# BaseBoard.net
KiCad netlist of a schematic drawn in EAGLE
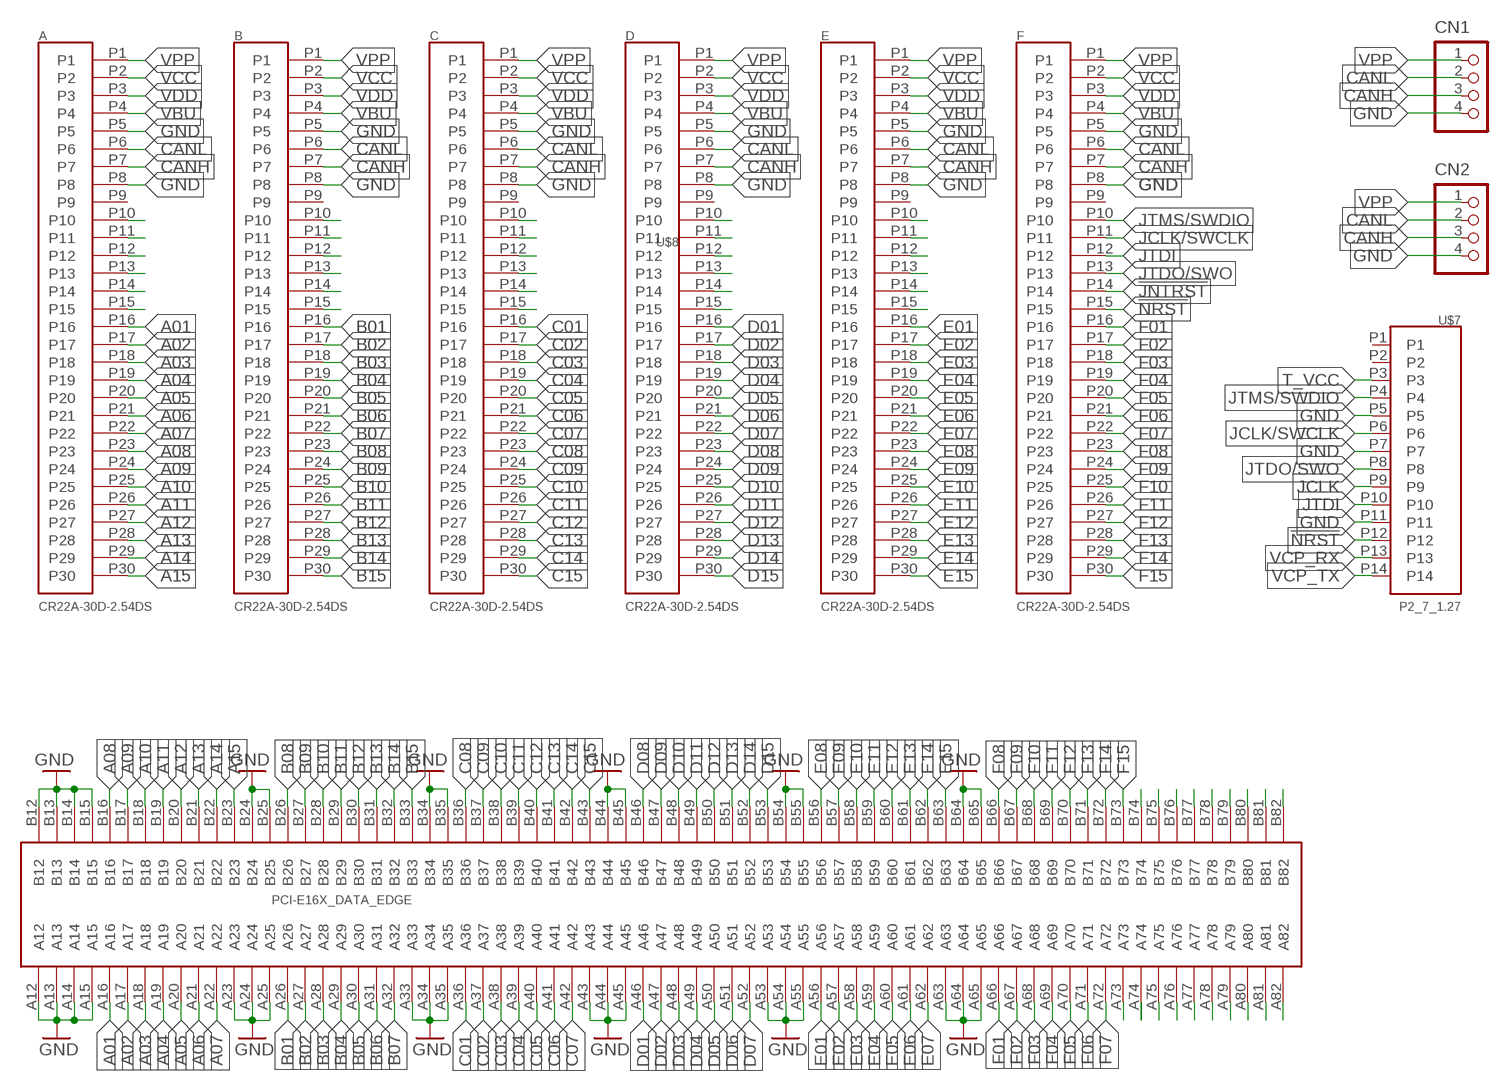
[diagram p0: schematic, sheet 1]

(export (version "E")
  (design (tool "Eeschema 10.0.6"))
  (components
    (comp (ref "A")
      (value "CR22A-30D-2.54DS")
      (footprint "eagle-import:CR22A-30D-2.54DS")
      (libsource (lib "eagle-import") (part "CR22A-30D-2.54DS"))
    )
    (comp (ref "B")
      (value "CR22A-30D-2.54DS")
      (footprint "eagle-import:CR22A-30D-2.54DS")
      (libsource (lib "eagle-import") (part "CR22A-30D-2.54DS"))
    )
    (comp (ref "C")
      (value "CR22A-30D-2.54DS")
      (footprint "eagle-import:CR22A-30D-2.54DS")
      (libsource (lib "eagle-import") (part "CR22A-30D-2.54DS"))
    )
    (comp (ref "CN1")
      (value "B4B-PH-K-S")
      (footprint "eagle-import:B4B-PH-K-S")
      (libsource (lib "eagle-import") (part "B4B-PH-K-S"))
    )
    (comp (ref "CN2")
      (value "B4B-PH-K-S")
      (footprint "eagle-import:B4B-PH-K-S")
      (libsource (lib "eagle-import") (part "B4B-PH-K-S"))
    )
    (comp (ref "D")
      (value "CR22A-30D-2.54DS")
      (footprint "eagle-import:CR22A-30D-2.54DS")
      (libsource (lib "eagle-import") (part "CR22A-30D-2.54DS"))
    )
    (comp (ref "E")
      (value "CR22A-30D-2.54DS")
      (footprint "eagle-import:CR22A-30D-2.54DS")
      (libsource (lib "eagle-import") (part "CR22A-30D-2.54DS"))
    )
    (comp (ref "F")
      (value "CR22A-30D-2.54DS")
      (footprint "eagle-import:CR22A-30D-2.54DS")
      (libsource (lib "eagle-import") (part "CR22A-30D-2.54DS"))
    )
    (comp (ref "U$7")
      (value "P2_7_1.27")
      (footprint "eagle-import:P2_7_1.27")
      (libsource (lib "eagle-import") (part "P2_7_1.27"))
    )
    (comp (ref "U$8")
      (value "PCI-E16X_DATA_EDGE")
      (footprint "eagle-import:PCI-E_164_DATA_EDGE")
      (libsource (lib "eagle-import") (part "PCI-E16X_DATA_EDGE"))
    )
  )
  (nets
    (net (code "1") (name "/~{JNTRST}") (class "Default")
      (node (ref "F") (pin "P14") (pinfunction "P14_P14") (pintype "bidirectional"))
    )
    (net (code "2") (name "/~{NRST}") (class "Default")
      (node (ref "F") (pin "P15") (pinfunction "P15_P15") (pintype "bidirectional"))
      (node (ref "U$7") (pin "P12") (pinfunction "P12_P12") (pintype "bidirectional"))
    )
    (net (code "3") (name "A01") (class "Default")
      (node (ref "A") (pin "P16") (pinfunction "P16_P16") (pintype "bidirectional"))
      (node (ref "U$8") (pin "A16") (pinfunction "A16_A16") (pintype "bidirectional"))
    )
    (net (code "4") (name "A02") (class "Default")
      (node (ref "A") (pin "P17") (pinfunction "P17_P17") (pintype "bidirectional"))
      (node (ref "U$8") (pin "A17") (pinfunction "A17_A17") (pintype "bidirectional"))
    )
    (net (code "5") (name "A03") (class "Default")
      (node (ref "A") (pin "P18") (pinfunction "P18_P18") (pintype "bidirectional"))
      (node (ref "U$8") (pin "A18") (pinfunction "A18_A18") (pintype "bidirectional"))
    )
    (net (code "6") (name "A04") (class "Default")
      (node (ref "A") (pin "P19") (pinfunction "P19_P19") (pintype "bidirectional"))
      (node (ref "U$8") (pin "A19") (pinfunction "A19_A19") (pintype "bidirectional"))
    )
    (net (code "7") (name "A05") (class "Default")
      (node (ref "A") (pin "P20") (pinfunction "P20_P20") (pintype "bidirectional"))
      (node (ref "U$8") (pin "A20") (pinfunction "A20_A20") (pintype "bidirectional"))
    )
    (net (code "8") (name "A06") (class "Default")
      (node (ref "A") (pin "P21") (pinfunction "P21_P21") (pintype "bidirectional"))
      (node (ref "U$8") (pin "A21") (pinfunction "A21_A21") (pintype "bidirectional"))
    )
    (net (code "9") (name "A07") (class "Default")
      (node (ref "A") (pin "P22") (pinfunction "P22_P22") (pintype "bidirectional"))
      (node (ref "U$8") (pin "A22") (pinfunction "A22_A22") (pintype "bidirectional"))
    )
    (net (code "10") (name "A08") (class "Default")
      (node (ref "A") (pin "P23") (pinfunction "P23_P23") (pintype "bidirectional"))
      (node (ref "U$8") (pin "B16") (pinfunction "B16_B16") (pintype "bidirectional"))
    )
    (net (code "11") (name "A09") (class "Default")
      (node (ref "A") (pin "P24") (pinfunction "P24_P24") (pintype "bidirectional"))
      (node (ref "U$8") (pin "B17") (pinfunction "B17_B17") (pintype "bidirectional"))
    )
    (net (code "12") (name "A10") (class "Default")
      (node (ref "A") (pin "P25") (pinfunction "P25_P25") (pintype "bidirectional"))
      (node (ref "U$8") (pin "B18") (pinfunction "B18_B18") (pintype "bidirectional"))
    )
    (net (code "13") (name "A11") (class "Default")
      (node (ref "A") (pin "P26") (pinfunction "P26_P26") (pintype "bidirectional"))
      (node (ref "U$8") (pin "B19") (pinfunction "B19_B19") (pintype "bidirectional"))
    )
    (net (code "14") (name "A12") (class "Default")
      (node (ref "A") (pin "P27") (pinfunction "P27_P27") (pintype "bidirectional"))
      (node (ref "U$8") (pin "B20") (pinfunction "B20_B20") (pintype "bidirectional"))
    )
    (net (code "15") (name "A13") (class "Default")
      (node (ref "A") (pin "P28") (pinfunction "P28_P28") (pintype "bidirectional"))
      (node (ref "U$8") (pin "B21") (pinfunction "B21_B21") (pintype "bidirectional"))
    )
    (net (code "16") (name "A14") (class "Default")
      (node (ref "A") (pin "P29") (pinfunction "P29_P29") (pintype "bidirectional"))
      (node (ref "U$8") (pin "B22") (pinfunction "B22_B22") (pintype "bidirectional"))
    )
    (net (code "17") (name "A15") (class "Default")
      (node (ref "A") (pin "P30") (pinfunction "P30_P30") (pintype "bidirectional"))
      (node (ref "U$8") (pin "B23") (pinfunction "B23_B23") (pintype "bidirectional"))
    )
    (net (code "18") (name "B01") (class "Default")
      (node (ref "B") (pin "P16") (pinfunction "P16_P16") (pintype "bidirectional"))
      (node (ref "U$8") (pin "A26") (pinfunction "A26_A26") (pintype "bidirectional"))
    )
    (net (code "19") (name "B02") (class "Default")
      (node (ref "B") (pin "P17") (pinfunction "P17_P17") (pintype "bidirectional"))
      (node (ref "U$8") (pin "A27") (pinfunction "A27_A27") (pintype "bidirectional"))
    )
    (net (code "20") (name "B03") (class "Default")
      (node (ref "B") (pin "P18") (pinfunction "P18_P18") (pintype "bidirectional"))
      (node (ref "U$8") (pin "A28") (pinfunction "A28_A28") (pintype "bidirectional"))
    )
    (net (code "21") (name "B04") (class "Default")
      (node (ref "B") (pin "P19") (pinfunction "P19_P19") (pintype "bidirectional"))
      (node (ref "U$8") (pin "A29") (pinfunction "A29_A29") (pintype "bidirectional"))
    )
    (net (code "22") (name "B05") (class "Default")
      (node (ref "B") (pin "P20") (pinfunction "P20_P20") (pintype "bidirectional"))
      (node (ref "U$8") (pin "A30") (pinfunction "A30_A30") (pintype "bidirectional"))
    )
    (net (code "23") (name "B06") (class "Default")
      (node (ref "B") (pin "P21") (pinfunction "P21_P21") (pintype "bidirectional"))
      (node (ref "U$8") (pin "A31") (pinfunction "A31_A31") (pintype "bidirectional"))
    )
    (net (code "24") (name "B07") (class "Default")
      (node (ref "B") (pin "P22") (pinfunction "P22_P22") (pintype "bidirectional"))
      (node (ref "U$8") (pin "A32") (pinfunction "A32_A32") (pintype "bidirectional"))
    )
    (net (code "25") (name "B08") (class "Default")
      (node (ref "B") (pin "P23") (pinfunction "P23_P23") (pintype "bidirectional"))
      (node (ref "U$8") (pin "B26") (pinfunction "B26_B26") (pintype "bidirectional"))
    )
    (net (code "26") (name "B09") (class "Default")
      (node (ref "B") (pin "P24") (pinfunction "P24_P24") (pintype "bidirectional"))
      (node (ref "U$8") (pin "B27") (pinfunction "B27_B27") (pintype "bidirectional"))
    )
    (net (code "27") (name "B10") (class "Default")
      (node (ref "B") (pin "P25") (pinfunction "P25_P25") (pintype "bidirectional"))
      (node (ref "U$8") (pin "B28") (pinfunction "B28_B28") (pintype "bidirectional"))
    )
    (net (code "28") (name "B11") (class "Default")
      (node (ref "B") (pin "P26") (pinfunction "P26_P26") (pintype "bidirectional"))
      (node (ref "U$8") (pin "B29") (pinfunction "B29_B29") (pintype "bidirectional"))
    )
    (net (code "29") (name "B12") (class "Default")
      (node (ref "B") (pin "P27") (pinfunction "P27_P27") (pintype "bidirectional"))
      (node (ref "U$8") (pin "B30") (pinfunction "B30_B30") (pintype "bidirectional"))
    )
    (net (code "30") (name "B13") (class "Default")
      (node (ref "B") (pin "P28") (pinfunction "P28_P28") (pintype "bidirectional"))
      (node (ref "U$8") (pin "B31") (pinfunction "B31_B31") (pintype "bidirectional"))
    )
    (net (code "31") (name "B14") (class "Default")
      (node (ref "B") (pin "P29") (pinfunction "P29_P29") (pintype "bidirectional"))
      (node (ref "U$8") (pin "B32") (pinfunction "B32_B32") (pintype "bidirectional"))
    )
    (net (code "32") (name "B15") (class "Default")
      (node (ref "B") (pin "P30") (pinfunction "P30_P30") (pintype "bidirectional"))
      (node (ref "U$8") (pin "B33") (pinfunction "B33_B33") (pintype "bidirectional"))
    )
    (net (code "33") (name "C01") (class "Default")
      (node (ref "C") (pin "P16") (pinfunction "P16_P16") (pintype "bidirectional"))
      (node (ref "U$8") (pin "A36") (pinfunction "A36_A36") (pintype "bidirectional"))
    )
    (net (code "34") (name "C02") (class "Default")
      (node (ref "C") (pin "P17") (pinfunction "P17_P17") (pintype "bidirectional"))
      (node (ref "U$8") (pin "A37") (pinfunction "A37_A37") (pintype "bidirectional"))
    )
    (net (code "35") (name "C03") (class "Default")
      (node (ref "C") (pin "P18") (pinfunction "P18_P18") (pintype "bidirectional"))
      (node (ref "U$8") (pin "A38") (pinfunction "A38_A38") (pintype "bidirectional"))
    )
    (net (code "36") (name "C04") (class "Default")
      (node (ref "C") (pin "P19") (pinfunction "P19_P19") (pintype "bidirectional"))
      (node (ref "U$8") (pin "A39") (pinfunction "A39_A39") (pintype "bidirectional"))
    )
    (net (code "37") (name "C05") (class "Default")
      (node (ref "C") (pin "P20") (pinfunction "P20_P20") (pintype "bidirectional"))
      (node (ref "U$8") (pin "A40") (pinfunction "A40_A40") (pintype "bidirectional"))
    )
    (net (code "38") (name "C06") (class "Default")
      (node (ref "C") (pin "P21") (pinfunction "P21_P21") (pintype "bidirectional"))
      (node (ref "U$8") (pin "A41") (pinfunction "A41_A41") (pintype "bidirectional"))
    )
    (net (code "39") (name "C07") (class "Default")
      (node (ref "C") (pin "P22") (pinfunction "P22_P22") (pintype "bidirectional"))
      (node (ref "U$8") (pin "A42") (pinfunction "A42_A42") (pintype "bidirectional"))
    )
    (net (code "40") (name "C08") (class "Default")
      (node (ref "C") (pin "P23") (pinfunction "P23_P23") (pintype "bidirectional"))
      (node (ref "U$8") (pin "B36") (pinfunction "B36_B36") (pintype "bidirectional"))
    )
    (net (code "41") (name "C09") (class "Default")
      (node (ref "C") (pin "P24") (pinfunction "P24_P24") (pintype "bidirectional"))
      (node (ref "U$8") (pin "B37") (pinfunction "B37_B37") (pintype "bidirectional"))
    )
    (net (code "42") (name "C10") (class "Default")
      (node (ref "C") (pin "P25") (pinfunction "P25_P25") (pintype "bidirectional"))
      (node (ref "U$8") (pin "B38") (pinfunction "B38_B38") (pintype "bidirectional"))
    )
    (net (code "43") (name "C11") (class "Default")
      (node (ref "C") (pin "P26") (pinfunction "P26_P26") (pintype "bidirectional"))
      (node (ref "U$8") (pin "B39") (pinfunction "B39_B39") (pintype "bidirectional"))
    )
    (net (code "44") (name "C12") (class "Default")
      (node (ref "C") (pin "P27") (pinfunction "P27_P27") (pintype "bidirectional"))
      (node (ref "U$8") (pin "B40") (pinfunction "B40_B40") (pintype "bidirectional"))
    )
    (net (code "45") (name "C13") (class "Default")
      (node (ref "C") (pin "P28") (pinfunction "P28_P28") (pintype "bidirectional"))
      (node (ref "U$8") (pin "B41") (pinfunction "B41_B41") (pintype "bidirectional"))
    )
    (net (code "46") (name "C14") (class "Default")
      (node (ref "C") (pin "P29") (pinfunction "P29_P29") (pintype "bidirectional"))
      (node (ref "U$8") (pin "B42") (pinfunction "B42_B42") (pintype "bidirectional"))
    )
    (net (code "47") (name "C15") (class "Default")
      (node (ref "C") (pin "P30") (pinfunction "P30_P30") (pintype "bidirectional"))
      (node (ref "U$8") (pin "B43") (pinfunction "B43_B43") (pintype "bidirectional"))
    )
    (net (code "48") (name "CANH") (class "Default")
      (node (ref "A") (pin "P7") (pinfunction "P7_P7") (pintype "bidirectional"))
      (node (ref "B") (pin "P7") (pinfunction "P7_P7") (pintype "bidirectional"))
      (node (ref "C") (pin "P7") (pinfunction "P7_P7") (pintype "bidirectional"))
      (node (ref "CN1") (pin "3") (pinfunction "3_3") (pintype "passive"))
      (node (ref "CN2") (pin "3") (pinfunction "3_3") (pintype "passive"))
      (node (ref "D") (pin "P7") (pinfunction "P7_P7") (pintype "bidirectional"))
      (node (ref "E") (pin "P7") (pinfunction "P7_P7") (pintype "bidirectional"))
      (node (ref "F") (pin "P7") (pinfunction "P7_P7") (pintype "bidirectional"))
    )
    (net (code "49") (name "CANL") (class "Default")
      (node (ref "A") (pin "P6") (pinfunction "P6_P6") (pintype "bidirectional"))
      (node (ref "B") (pin "P6") (pinfunction "P6_P6") (pintype "bidirectional"))
      (node (ref "C") (pin "P6") (pinfunction "P6_P6") (pintype "bidirectional"))
      (node (ref "CN1") (pin "2") (pinfunction "2_2") (pintype "passive"))
      (node (ref "CN2") (pin "2") (pinfunction "2_2") (pintype "passive"))
      (node (ref "D") (pin "P6") (pinfunction "P6_P6") (pintype "bidirectional"))
      (node (ref "E") (pin "P6") (pinfunction "P6_P6") (pintype "bidirectional"))
      (node (ref "F") (pin "P6") (pinfunction "P6_P6") (pintype "bidirectional"))
    )
    (net (code "50") (name "D01") (class "Default")
      (node (ref "D") (pin "P16") (pinfunction "P16_P16") (pintype "bidirectional"))
      (node (ref "U$8") (pin "A46") (pinfunction "A46_A46") (pintype "bidirectional"))
    )
    (net (code "51") (name "D02") (class "Default")
      (node (ref "D") (pin "P17") (pinfunction "P17_P17") (pintype "bidirectional"))
      (node (ref "U$8") (pin "A47") (pinfunction "A47_A47") (pintype "bidirectional"))
    )
    (net (code "52") (name "D03") (class "Default")
      (node (ref "D") (pin "P18") (pinfunction "P18_P18") (pintype "bidirectional"))
      (node (ref "U$8") (pin "A48") (pinfunction "A48_A48") (pintype "bidirectional"))
    )
    (net (code "53") (name "D04") (class "Default")
      (node (ref "D") (pin "P19") (pinfunction "P19_P19") (pintype "bidirectional"))
      (node (ref "U$8") (pin "A49") (pinfunction "A49_A49") (pintype "bidirectional"))
    )
    (net (code "54") (name "D05") (class "Default")
      (node (ref "D") (pin "P20") (pinfunction "P20_P20") (pintype "bidirectional"))
      (node (ref "U$8") (pin "A50") (pinfunction "A50_A50") (pintype "bidirectional"))
    )
    (net (code "55") (name "D06") (class "Default")
      (node (ref "D") (pin "P21") (pinfunction "P21_P21") (pintype "bidirectional"))
      (node (ref "U$8") (pin "A51") (pinfunction "A51_A51") (pintype "bidirectional"))
    )
    (net (code "56") (name "D07") (class "Default")
      (node (ref "D") (pin "P22") (pinfunction "P22_P22") (pintype "bidirectional"))
      (node (ref "U$8") (pin "A52") (pinfunction "A52_A52") (pintype "bidirectional"))
    )
    (net (code "57") (name "D08") (class "Default")
      (node (ref "D") (pin "P23") (pinfunction "P23_P23") (pintype "bidirectional"))
      (node (ref "U$8") (pin "B46") (pinfunction "B46_B46") (pintype "bidirectional"))
    )
    (net (code "58") (name "D09") (class "Default")
      (node (ref "D") (pin "P24") (pinfunction "P24_P24") (pintype "bidirectional"))
      (node (ref "U$8") (pin "B47") (pinfunction "B47_B47") (pintype "bidirectional"))
    )
    (net (code "59") (name "D10") (class "Default")
      (node (ref "D") (pin "P25") (pinfunction "P25_P25") (pintype "bidirectional"))
      (node (ref "U$8") (pin "B48") (pinfunction "B48_B48") (pintype "bidirectional"))
    )
    (net (code "60") (name "D11") (class "Default")
      (node (ref "D") (pin "P26") (pinfunction "P26_P26") (pintype "bidirectional"))
      (node (ref "U$8") (pin "B49") (pinfunction "B49_B49") (pintype "bidirectional"))
    )
    (net (code "61") (name "D12") (class "Default")
      (node (ref "D") (pin "P27") (pinfunction "P27_P27") (pintype "bidirectional"))
      (node (ref "U$8") (pin "B50") (pinfunction "B50_B50") (pintype "bidirectional"))
    )
    (net (code "62") (name "D13") (class "Default")
      (node (ref "D") (pin "P28") (pinfunction "P28_P28") (pintype "bidirectional"))
      (node (ref "U$8") (pin "B51") (pinfunction "B51_B51") (pintype "bidirectional"))
    )
    (net (code "63") (name "D14") (class "Default")
      (node (ref "D") (pin "P29") (pinfunction "P29_P29") (pintype "bidirectional"))
      (node (ref "U$8") (pin "B52") (pinfunction "B52_B52") (pintype "bidirectional"))
    )
    (net (code "64") (name "D15") (class "Default")
      (node (ref "D") (pin "P30") (pinfunction "P30_P30") (pintype "bidirectional"))
      (node (ref "U$8") (pin "B53") (pinfunction "B53_B53") (pintype "bidirectional"))
    )
    (net (code "65") (name "E01") (class "Default")
      (node (ref "E") (pin "P16") (pinfunction "P16_P16") (pintype "bidirectional"))
      (node (ref "U$8") (pin "A56") (pinfunction "A56_A56") (pintype "bidirectional"))
    )
    (net (code "66") (name "E02") (class "Default")
      (node (ref "E") (pin "P17") (pinfunction "P17_P17") (pintype "bidirectional"))
      (node (ref "U$8") (pin "A57") (pinfunction "A57_A57") (pintype "bidirectional"))
    )
    (net (code "67") (name "E03") (class "Default")
      (node (ref "E") (pin "P18") (pinfunction "P18_P18") (pintype "bidirectional"))
      (node (ref "U$8") (pin "A58") (pinfunction "A58_A58") (pintype "bidirectional"))
    )
    (net (code "68") (name "E04") (class "Default")
      (node (ref "E") (pin "P19") (pinfunction "P19_P19") (pintype "bidirectional"))
      (node (ref "U$8") (pin "A59") (pinfunction "A59_A59") (pintype "bidirectional"))
    )
    (net (code "69") (name "E05") (class "Default")
      (node (ref "E") (pin "P20") (pinfunction "P20_P20") (pintype "bidirectional"))
      (node (ref "U$8") (pin "A60") (pinfunction "A60_A60") (pintype "bidirectional"))
    )
    (net (code "70") (name "E06") (class "Default")
      (node (ref "E") (pin "P21") (pinfunction "P21_P21") (pintype "bidirectional"))
      (node (ref "U$8") (pin "A61") (pinfunction "A61_A61") (pintype "bidirectional"))
    )
    (net (code "71") (name "E07") (class "Default")
      (node (ref "E") (pin "P22") (pinfunction "P22_P22") (pintype "bidirectional"))
      (node (ref "U$8") (pin "A62") (pinfunction "A62_A62") (pintype "bidirectional"))
    )
    (net (code "72") (name "E08") (class "Default")
      (node (ref "E") (pin "P23") (pinfunction "P23_P23") (pintype "bidirectional"))
      (node (ref "U$8") (pin "B56") (pinfunction "B56_B56") (pintype "bidirectional"))
    )
    (net (code "73") (name "E09") (class "Default")
      (node (ref "E") (pin "P24") (pinfunction "P24_P24") (pintype "bidirectional"))
      (node (ref "U$8") (pin "B57") (pinfunction "B57_B57") (pintype "bidirectional"))
    )
    (net (code "74") (name "E10") (class "Default")
      (node (ref "E") (pin "P25") (pinfunction "P25_P25") (pintype "bidirectional"))
      (node (ref "U$8") (pin "B58") (pinfunction "B58_B58") (pintype "bidirectional"))
    )
    (net (code "75") (name "E11") (class "Default")
      (node (ref "E") (pin "P26") (pinfunction "P26_P26") (pintype "bidirectional"))
      (node (ref "U$8") (pin "B59") (pinfunction "B59_B59") (pintype "bidirectional"))
    )
    (net (code "76") (name "E12") (class "Default")
      (node (ref "E") (pin "P27") (pinfunction "P27_P27") (pintype "bidirectional"))
      (node (ref "U$8") (pin "B60") (pinfunction "B60_B60") (pintype "bidirectional"))
    )
    (net (code "77") (name "E13") (class "Default")
      (node (ref "E") (pin "P28") (pinfunction "P28_P28") (pintype "bidirectional"))
      (node (ref "U$8") (pin "B61") (pinfunction "B61_B61") (pintype "bidirectional"))
    )
    (net (code "78") (name "E14") (class "Default")
      (node (ref "E") (pin "P29") (pinfunction "P29_P29") (pintype "bidirectional"))
      (node (ref "U$8") (pin "B62") (pinfunction "B62_B62") (pintype "bidirectional"))
    )
    (net (code "79") (name "E15") (class "Default")
      (node (ref "E") (pin "P30") (pinfunction "P30_P30") (pintype "bidirectional"))
      (node (ref "U$8") (pin "B63") (pinfunction "B63_B63") (pintype "bidirectional"))
    )
    (net (code "80") (name "F01") (class "Default")
      (node (ref "F") (pin "P16") (pinfunction "P16_P16") (pintype "bidirectional"))
      (node (ref "U$8") (pin "A66") (pinfunction "A66_A66") (pintype "bidirectional"))
    )
    (net (code "81") (name "F02") (class "Default")
      (node (ref "F") (pin "P17") (pinfunction "P17_P17") (pintype "bidirectional"))
      (node (ref "U$8") (pin "A67") (pinfunction "A67_A67") (pintype "bidirectional"))
    )
    (net (code "82") (name "F03") (class "Default")
      (node (ref "F") (pin "P18") (pinfunction "P18_P18") (pintype "bidirectional"))
      (node (ref "U$8") (pin "A68") (pinfunction "A68_A68") (pintype "bidirectional"))
    )
    (net (code "83") (name "F04") (class "Default")
      (node (ref "F") (pin "P19") (pinfunction "P19_P19") (pintype "bidirectional"))
      (node (ref "U$8") (pin "A69") (pinfunction "A69_A69") (pintype "bidirectional"))
    )
    (net (code "84") (name "F05") (class "Default")
      (node (ref "F") (pin "P20") (pinfunction "P20_P20") (pintype "bidirectional"))
      (node (ref "U$8") (pin "A70") (pinfunction "A70_A70") (pintype "bidirectional"))
    )
    (net (code "85") (name "F06") (class "Default")
      (node (ref "F") (pin "P21") (pinfunction "P21_P21") (pintype "bidirectional"))
      (node (ref "U$8") (pin "A71") (pinfunction "A71_A71") (pintype "bidirectional"))
    )
    (net (code "86") (name "F07") (class "Default")
      (node (ref "F") (pin "P22") (pinfunction "P22_P22") (pintype "bidirectional"))
      (node (ref "U$8") (pin "A72") (pinfunction "A72_A72") (pintype "bidirectional"))
    )
    (net (code "87") (name "F08") (class "Default")
      (node (ref "F") (pin "P23") (pinfunction "P23_P23") (pintype "bidirectional"))
      (node (ref "U$8") (pin "B66") (pinfunction "B66_B66") (pintype "bidirectional"))
    )
    (net (code "88") (name "F09") (class "Default")
      (node (ref "F") (pin "P24") (pinfunction "P24_P24") (pintype "bidirectional"))
      (node (ref "U$8") (pin "B67") (pinfunction "B67_B67") (pintype "bidirectional"))
    )
    (net (code "89") (name "F10") (class "Default")
      (node (ref "F") (pin "P25") (pinfunction "P25_P25") (pintype "bidirectional"))
      (node (ref "U$8") (pin "B68") (pinfunction "B68_B68") (pintype "bidirectional"))
    )
    (net (code "90") (name "F11") (class "Default")
      (node (ref "F") (pin "P26") (pinfunction "P26_P26") (pintype "bidirectional"))
      (node (ref "U$8") (pin "B69") (pinfunction "B69_B69") (pintype "bidirectional"))
    )
    (net (code "91") (name "F12") (class "Default")
      (node (ref "F") (pin "P27") (pinfunction "P27_P27") (pintype "bidirectional"))
      (node (ref "U$8") (pin "B70") (pinfunction "B70_B70") (pintype "bidirectional"))
    )
    (net (code "92") (name "F13") (class "Default")
      (node (ref "F") (pin "P28") (pinfunction "P28_P28") (pintype "bidirectional"))
      (node (ref "U$8") (pin "B71") (pinfunction "B71_B71") (pintype "bidirectional"))
    )
    (net (code "93") (name "F14") (class "Default")
      (node (ref "F") (pin "P29") (pinfunction "P29_P29") (pintype "bidirectional"))
      (node (ref "U$8") (pin "B72") (pinfunction "B72_B72") (pintype "bidirectional"))
    )
    (net (code "94") (name "F15") (class "Default")
      (node (ref "F") (pin "P30") (pinfunction "P30_P30") (pintype "bidirectional"))
      (node (ref "U$8") (pin "B73") (pinfunction "B73_B73") (pintype "bidirectional"))
    )
    (net (code "95") (name "GND") (class "Default")
      (node (ref "A") (pin "P5") (pinfunction "P5_P5") (pintype "bidirectional"))
      (node (ref "A") (pin "P8") (pinfunction "P8_P8") (pintype "bidirectional"))
      (node (ref "B") (pin "P5") (pinfunction "P5_P5") (pintype "bidirectional"))
      (node (ref "B") (pin "P8") (pinfunction "P8_P8") (pintype "bidirectional"))
      (node (ref "C") (pin "P5") (pinfunction "P5_P5") (pintype "bidirectional"))
      (node (ref "C") (pin "P8") (pinfunction "P8_P8") (pintype "bidirectional"))
      (node (ref "CN1") (pin "4") (pinfunction "4_4") (pintype "passive"))
      (node (ref "CN2") (pin "4") (pinfunction "4_4") (pintype "passive"))
      (node (ref "D") (pin "P5") (pinfunction "P5_P5") (pintype "bidirectional"))
      (node (ref "D") (pin "P8") (pinfunction "P8_P8") (pintype "bidirectional"))
      (node (ref "E") (pin "P5") (pinfunction "P5_P5") (pintype "bidirectional"))
      (node (ref "E") (pin "P8") (pinfunction "P8_P8") (pintype "bidirectional"))
      (node (ref "F") (pin "P5") (pinfunction "P5_P5") (pintype "bidirectional"))
      (node (ref "F") (pin "P8") (pinfunction "P8_P8") (pintype "bidirectional"))
      (node (ref "U$7") (pin "P11") (pinfunction "P11_P11") (pintype "bidirectional"))
      (node (ref "U$7") (pin "P5") (pinfunction "P5_P5") (pintype "bidirectional"))
      (node (ref "U$7") (pin "P7") (pinfunction "P7_P7") (pintype "bidirectional"))
      (node (ref "U$8") (pin "A12") (pinfunction "A12_A12") (pintype "bidirectional"))
      (node (ref "U$8") (pin "A13") (pinfunction "A13_A13") (pintype "bidirectional"))
      (node (ref "U$8") (pin "A14") (pinfunction "A14_A14") (pintype "bidirectional"))
      (node (ref "U$8") (pin "A15") (pinfunction "A15_A15") (pintype "bidirectional"))
      (node (ref "U$8") (pin "A23") (pinfunction "A23_A23") (pintype "bidirectional"))
      (node (ref "U$8") (pin "A24") (pinfunction "A24_A24") (pintype "bidirectional"))
      (node (ref "U$8") (pin "A25") (pinfunction "A25_A25") (pintype "bidirectional"))
      (node (ref "U$8") (pin "A33") (pinfunction "A33_A33") (pintype "bidirectional"))
      (node (ref "U$8") (pin "A34") (pinfunction "A34_A34") (pintype "bidirectional"))
      (node (ref "U$8") (pin "A35") (pinfunction "A35_A35") (pintype "bidirectional"))
      (node (ref "U$8") (pin "A43") (pinfunction "A43_A43") (pintype "bidirectional"))
      (node (ref "U$8") (pin "A44") (pinfunction "A44_A44") (pintype "bidirectional"))
      (node (ref "U$8") (pin "A45") (pinfunction "A45_A45") (pintype "bidirectional"))
      (node (ref "U$8") (pin "A53") (pinfunction "A53_A53") (pintype "bidirectional"))
      (node (ref "U$8") (pin "A54") (pinfunction "A54_A54") (pintype "bidirectional"))
      (node (ref "U$8") (pin "A55") (pinfunction "A55_A55") (pintype "bidirectional"))
      (node (ref "U$8") (pin "A63") (pinfunction "A63_A63") (pintype "bidirectional"))
      (node (ref "U$8") (pin "A64") (pinfunction "A64_A64") (pintype "bidirectional"))
      (node (ref "U$8") (pin "A65") (pinfunction "A65_A65") (pintype "bidirectional"))
      (node (ref "U$8") (pin "B12") (pinfunction "B12_B12") (pintype "bidirectional"))
      (node (ref "U$8") (pin "B13") (pinfunction "B13_B13") (pintype "bidirectional"))
      (node (ref "U$8") (pin "B14") (pinfunction "B14_B14") (pintype "bidirectional"))
      (node (ref "U$8") (pin "B15") (pinfunction "B15_B15") (pintype "bidirectional"))
      (node (ref "U$8") (pin "B24") (pinfunction "B24_B24") (pintype "bidirectional"))
      (node (ref "U$8") (pin "B25") (pinfunction "B25_B25") (pintype "bidirectional"))
      (node (ref "U$8") (pin "B34") (pinfunction "B34_B34") (pintype "bidirectional"))
      (node (ref "U$8") (pin "B35") (pinfunction "B35_B35") (pintype "bidirectional"))
      (node (ref "U$8") (pin "B44") (pinfunction "B44_B44") (pintype "bidirectional"))
      (node (ref "U$8") (pin "B45") (pinfunction "B45_B45") (pintype "bidirectional"))
      (node (ref "U$8") (pin "B54") (pinfunction "B54_B54") (pintype "bidirectional"))
      (node (ref "U$8") (pin "B55") (pinfunction "B55_B55") (pintype "bidirectional"))
      (node (ref "U$8") (pin "B64") (pinfunction "B64_B64") (pintype "bidirectional"))
      (node (ref "U$8") (pin "B65") (pinfunction "B65_B65") (pintype "bidirectional"))
    )
    (net (code "96") (name "JCLK") (class "Default")
      (node (ref "U$7") (pin "P9") (pinfunction "P9_P9") (pintype "bidirectional"))
    )
    (net (code "97") (name "JCLK{slash}SWCLK") (class "Default")
      (node (ref "F") (pin "P11") (pinfunction "P11_P11") (pintype "bidirectional"))
      (node (ref "U$7") (pin "P6") (pinfunction "P6_P6") (pintype "bidirectional"))
    )
    (net (code "98") (name "JTDI") (class "Default")
      (node (ref "F") (pin "P12") (pinfunction "P12_P12") (pintype "bidirectional"))
      (node (ref "U$7") (pin "P10") (pinfunction "P10_P10") (pintype "bidirectional"))
    )
    (net (code "99") (name "JTDO{slash}SWO") (class "Default")
      (node (ref "F") (pin "P13") (pinfunction "P13_P13") (pintype "bidirectional"))
      (node (ref "U$7") (pin "P8") (pinfunction "P8_P8") (pintype "bidirectional"))
    )
    (net (code "100") (name "JTMS{slash}SWDIO") (class "Default")
      (node (ref "F") (pin "P10") (pinfunction "P10_P10") (pintype "bidirectional"))
      (node (ref "U$7") (pin "P4") (pinfunction "P4_P4") (pintype "bidirectional"))
    )
    (net (code "101") (name "T_VCC") (class "Default")
      (node (ref "U$7") (pin "P3") (pinfunction "P3_P3") (pintype "bidirectional"))
    )
    (net (code "102") (name "VBU") (class "Default")
      (node (ref "A") (pin "P4") (pinfunction "P4_P4") (pintype "bidirectional"))
      (node (ref "B") (pin "P4") (pinfunction "P4_P4") (pintype "bidirectional"))
      (node (ref "C") (pin "P4") (pinfunction "P4_P4") (pintype "bidirectional"))
      (node (ref "D") (pin "P4") (pinfunction "P4_P4") (pintype "bidirectional"))
      (node (ref "E") (pin "P4") (pinfunction "P4_P4") (pintype "bidirectional"))
      (node (ref "F") (pin "P4") (pinfunction "P4_P4") (pintype "bidirectional"))
    )
    (net (code "103") (name "VCC") (class "Default")
      (node (ref "A") (pin "P2") (pinfunction "P2_P2") (pintype "bidirectional"))
      (node (ref "B") (pin "P2") (pinfunction "P2_P2") (pintype "bidirectional"))
      (node (ref "C") (pin "P2") (pinfunction "P2_P2") (pintype "bidirectional"))
      (node (ref "D") (pin "P2") (pinfunction "P2_P2") (pintype "bidirectional"))
      (node (ref "E") (pin "P2") (pinfunction "P2_P2") (pintype "bidirectional"))
      (node (ref "F") (pin "P2") (pinfunction "P2_P2") (pintype "bidirectional"))
    )
    (net (code "104") (name "VCP_RX") (class "Default")
      (node (ref "U$7") (pin "P13") (pinfunction "P13_P13") (pintype "bidirectional"))
    )
    (net (code "105") (name "VCP_TX") (class "Default")
      (node (ref "U$7") (pin "P14") (pinfunction "P14_P14") (pintype "bidirectional"))
    )
    (net (code "106") (name "VDD") (class "Default")
      (node (ref "A") (pin "P3") (pinfunction "P3_P3") (pintype "bidirectional"))
      (node (ref "B") (pin "P3") (pinfunction "P3_P3") (pintype "bidirectional"))
      (node (ref "C") (pin "P3") (pinfunction "P3_P3") (pintype "bidirectional"))
      (node (ref "D") (pin "P3") (pinfunction "P3_P3") (pintype "bidirectional"))
      (node (ref "E") (pin "P3") (pinfunction "P3_P3") (pintype "bidirectional"))
      (node (ref "F") (pin "P3") (pinfunction "P3_P3") (pintype "bidirectional"))
    )
    (net (code "107") (name "VPP") (class "Default")
      (node (ref "A") (pin "P1") (pinfunction "P1_P1") (pintype "bidirectional"))
      (node (ref "B") (pin "P1") (pinfunction "P1_P1") (pintype "bidirectional"))
      (node (ref "C") (pin "P1") (pinfunction "P1_P1") (pintype "bidirectional"))
      (node (ref "CN1") (pin "1") (pinfunction "1_1") (pintype "passive"))
      (node (ref "CN2") (pin "1") (pinfunction "1_1") (pintype "passive"))
      (node (ref "D") (pin "P1") (pinfunction "P1_P1") (pintype "bidirectional"))
      (node (ref "E") (pin "P1") (pinfunction "P1_P1") (pintype "bidirectional"))
      (node (ref "F") (pin "P1") (pinfunction "P1_P1") (pintype "bidirectional"))
    )
    (net (code "108") (name "unconnected-(A-PadP9)") (class "Default")
      (node (ref "A") (pin "P9") (pinfunction "P9_P9") (pintype "bidirectional"))
    )
    (net (code "109") (name "unconnected-(A-PadP10)") (class "Default")
      (node (ref "A") (pin "P10") (pinfunction "P10_P10") (pintype "bidirectional"))
    )
    (net (code "110") (name "unconnected-(A-PadP11)") (class "Default")
      (node (ref "A") (pin "P11") (pinfunction "P11_P11") (pintype "bidirectional"))
    )
    (net (code "111") (name "unconnected-(A-PadP12)") (class "Default")
      (node (ref "A") (pin "P12") (pinfunction "P12_P12") (pintype "bidirectional"))
    )
    (net (code "112") (name "unconnected-(A-PadP13)") (class "Default")
      (node (ref "A") (pin "P13") (pinfunction "P13_P13") (pintype "bidirectional"))
    )
    (net (code "113") (name "unconnected-(A-PadP14)") (class "Default")
      (node (ref "A") (pin "P14") (pinfunction "P14_P14") (pintype "bidirectional"))
    )
    (net (code "114") (name "unconnected-(A-PadP15)") (class "Default")
      (node (ref "A") (pin "P15") (pinfunction "P15_P15") (pintype "bidirectional"))
    )
    (net (code "115") (name "unconnected-(B-PadP9)") (class "Default")
      (node (ref "B") (pin "P9") (pinfunction "P9_P9") (pintype "bidirectional"))
    )
    (net (code "116") (name "unconnected-(B-PadP10)") (class "Default")
      (node (ref "B") (pin "P10") (pinfunction "P10_P10") (pintype "bidirectional"))
    )
    (net (code "117") (name "unconnected-(B-PadP11)") (class "Default")
      (node (ref "B") (pin "P11") (pinfunction "P11_P11") (pintype "bidirectional"))
    )
    (net (code "118") (name "unconnected-(B-PadP12)") (class "Default")
      (node (ref "B") (pin "P12") (pinfunction "P12_P12") (pintype "bidirectional"))
    )
    (net (code "119") (name "unconnected-(B-PadP13)") (class "Default")
      (node (ref "B") (pin "P13") (pinfunction "P13_P13") (pintype "bidirectional"))
    )
    (net (code "120") (name "unconnected-(B-PadP14)") (class "Default")
      (node (ref "B") (pin "P14") (pinfunction "P14_P14") (pintype "bidirectional"))
    )
    (net (code "121") (name "unconnected-(B-PadP15)") (class "Default")
      (node (ref "B") (pin "P15") (pinfunction "P15_P15") (pintype "bidirectional"))
    )
    (net (code "122") (name "unconnected-(C-PadP9)") (class "Default")
      (node (ref "C") (pin "P9") (pinfunction "P9_P9") (pintype "bidirectional"))
    )
    (net (code "123") (name "unconnected-(C-PadP10)") (class "Default")
      (node (ref "C") (pin "P10") (pinfunction "P10_P10") (pintype "bidirectional"))
    )
    (net (code "124") (name "unconnected-(C-PadP11)") (class "Default")
      (node (ref "C") (pin "P11") (pinfunction "P11_P11") (pintype "bidirectional"))
    )
    (net (code "125") (name "unconnected-(C-PadP12)") (class "Default")
      (node (ref "C") (pin "P12") (pinfunction "P12_P12") (pintype "bidirectional"))
    )
    (net (code "126") (name "unconnected-(C-PadP13)") (class "Default")
      (node (ref "C") (pin "P13") (pinfunction "P13_P13") (pintype "bidirectional"))
    )
    (net (code "127") (name "unconnected-(C-PadP14)") (class "Default")
      (node (ref "C") (pin "P14") (pinfunction "P14_P14") (pintype "bidirectional"))
    )
    (net (code "128") (name "unconnected-(C-PadP15)") (class "Default")
      (node (ref "C") (pin "P15") (pinfunction "P15_P15") (pintype "bidirectional"))
    )
    (net (code "129") (name "unconnected-(D-PadP9)") (class "Default")
      (node (ref "D") (pin "P9") (pinfunction "P9_P9") (pintype "bidirectional"))
    )
    (net (code "130") (name "unconnected-(D-PadP10)") (class "Default")
      (node (ref "D") (pin "P10") (pinfunction "P10_P10") (pintype "bidirectional"))
    )
    (net (code "131") (name "unconnected-(D-PadP11)") (class "Default")
      (node (ref "D") (pin "P11") (pinfunction "P11_P11") (pintype "bidirectional"))
    )
    (net (code "132") (name "unconnected-(D-PadP12)") (class "Default")
      (node (ref "D") (pin "P12") (pinfunction "P12_P12") (pintype "bidirectional"))
    )
    (net (code "133") (name "unconnected-(D-PadP13)") (class "Default")
      (node (ref "D") (pin "P13") (pinfunction "P13_P13") (pintype "bidirectional"))
    )
    (net (code "134") (name "unconnected-(D-PadP14)") (class "Default")
      (node (ref "D") (pin "P14") (pinfunction "P14_P14") (pintype "bidirectional"))
    )
    (net (code "135") (name "unconnected-(D-PadP15)") (class "Default")
      (node (ref "D") (pin "P15") (pinfunction "P15_P15") (pintype "bidirectional"))
    )
    (net (code "136") (name "unconnected-(E-PadP9)") (class "Default")
      (node (ref "E") (pin "P9") (pinfunction "P9_P9") (pintype "bidirectional"))
    )
    (net (code "137") (name "unconnected-(E-PadP10)") (class "Default")
      (node (ref "E") (pin "P10") (pinfunction "P10_P10") (pintype "bidirectional"))
    )
    (net (code "138") (name "unconnected-(E-PadP11)") (class "Default")
      (node (ref "E") (pin "P11") (pinfunction "P11_P11") (pintype "bidirectional"))
    )
    (net (code "139") (name "unconnected-(E-PadP12)") (class "Default")
      (node (ref "E") (pin "P12") (pinfunction "P12_P12") (pintype "bidirectional"))
    )
    (net (code "140") (name "unconnected-(E-PadP13)") (class "Default")
      (node (ref "E") (pin "P13") (pinfunction "P13_P13") (pintype "bidirectional"))
    )
    (net (code "141") (name "unconnected-(E-PadP14)") (class "Default")
      (node (ref "E") (pin "P14") (pinfunction "P14_P14") (pintype "bidirectional"))
    )
    (net (code "142") (name "unconnected-(E-PadP15)") (class "Default")
      (node (ref "E") (pin "P15") (pinfunction "P15_P15") (pintype "bidirectional"))
    )
    (net (code "143") (name "unconnected-(F-PadP9)") (class "Default")
      (node (ref "F") (pin "P9") (pinfunction "P9_P9") (pintype "bidirectional"))
    )
    (net (code "144") (name "unconnected-(U$7-PadP1)") (class "Default")
      (node (ref "U$7") (pin "P1") (pinfunction "P1_P1") (pintype "bidirectional"))
    )
    (net (code "145") (name "unconnected-(U$7-PadP2)") (class "Default")
      (node (ref "U$7") (pin "P2") (pinfunction "P2_P2") (pintype "bidirectional"))
    )
    (net (code "146") (name "unconnected-(U$8-PadA73)") (class "Default")
      (node (ref "U$8") (pin "A73") (pinfunction "A73_A73") (pintype "bidirectional"))
    )
    (net (code "147") (name "unconnected-(U$8-PadA74)") (class "Default")
      (node (ref "U$8") (pin "A74") (pinfunction "A74_A74") (pintype "bidirectional"))
    )
    (net (code "148") (name "unconnected-(U$8-PadA75)") (class "Default")
      (node (ref "U$8") (pin "A75") (pinfunction "A75_A75") (pintype "bidirectional"))
    )
    (net (code "149") (name "unconnected-(U$8-PadA76)") (class "Default")
      (node (ref "U$8") (pin "A76") (pinfunction "A76_A76") (pintype "bidirectional"))
    )
    (net (code "150") (name "unconnected-(U$8-PadA77)") (class "Default")
      (node (ref "U$8") (pin "A77") (pinfunction "A77_A77") (pintype "bidirectional"))
    )
    (net (code "151") (name "unconnected-(U$8-PadA78)") (class "Default")
      (node (ref "U$8") (pin "A78") (pinfunction "A78_A78") (pintype "bidirectional"))
    )
    (net (code "152") (name "unconnected-(U$8-PadA79)") (class "Default")
      (node (ref "U$8") (pin "A79") (pinfunction "A79_A79") (pintype "bidirectional"))
    )
    (net (code "153") (name "unconnected-(U$8-PadA80)") (class "Default")
      (node (ref "U$8") (pin "A80") (pinfunction "A80_A80") (pintype "bidirectional"))
    )
    (net (code "154") (name "unconnected-(U$8-PadA81)") (class "Default")
      (node (ref "U$8") (pin "A81") (pinfunction "A81_A81") (pintype "bidirectional"))
    )
    (net (code "155") (name "unconnected-(U$8-PadA82)") (class "Default")
      (node (ref "U$8") (pin "A82") (pinfunction "A82_A82") (pintype "bidirectional"))
    )
    (net (code "156") (name "unconnected-(U$8-PadB74)") (class "Default")
      (node (ref "U$8") (pin "B74") (pinfunction "B74_B74") (pintype "bidirectional"))
    )
    (net (code "157") (name "unconnected-(U$8-PadB75)") (class "Default")
      (node (ref "U$8") (pin "B75") (pinfunction "B75_B75") (pintype "bidirectional"))
    )
    (net (code "158") (name "unconnected-(U$8-PadB76)") (class "Default")
      (node (ref "U$8") (pin "B76") (pinfunction "B76_B76") (pintype "bidirectional"))
    )
    (net (code "159") (name "unconnected-(U$8-PadB77)") (class "Default")
      (node (ref "U$8") (pin "B77") (pinfunction "B77_B77") (pintype "bidirectional"))
    )
    (net (code "160") (name "unconnected-(U$8-PadB78)") (class "Default")
      (node (ref "U$8") (pin "B78") (pinfunction "B78_B78") (pintype "bidirectional"))
    )
    (net (code "161") (name "unconnected-(U$8-PadB79)") (class "Default")
      (node (ref "U$8") (pin "B79") (pinfunction "B79_B79") (pintype "bidirectional"))
    )
    (net (code "162") (name "unconnected-(U$8-PadB80)") (class "Default")
      (node (ref "U$8") (pin "B80") (pinfunction "B80_B80") (pintype "bidirectional"))
    )
    (net (code "163") (name "unconnected-(U$8-PadB81)") (class "Default")
      (node (ref "U$8") (pin "B81") (pinfunction "B81_B81") (pintype "bidirectional"))
    )
    (net (code "164") (name "unconnected-(U$8-PadB82)") (class "Default")
      (node (ref "U$8") (pin "B82") (pinfunction "B82_B82") (pintype "bidirectional"))
    )
  )
)
